# M5_Display_COMM.net
KiCad netlist of a schematic drawn in Altium Designer
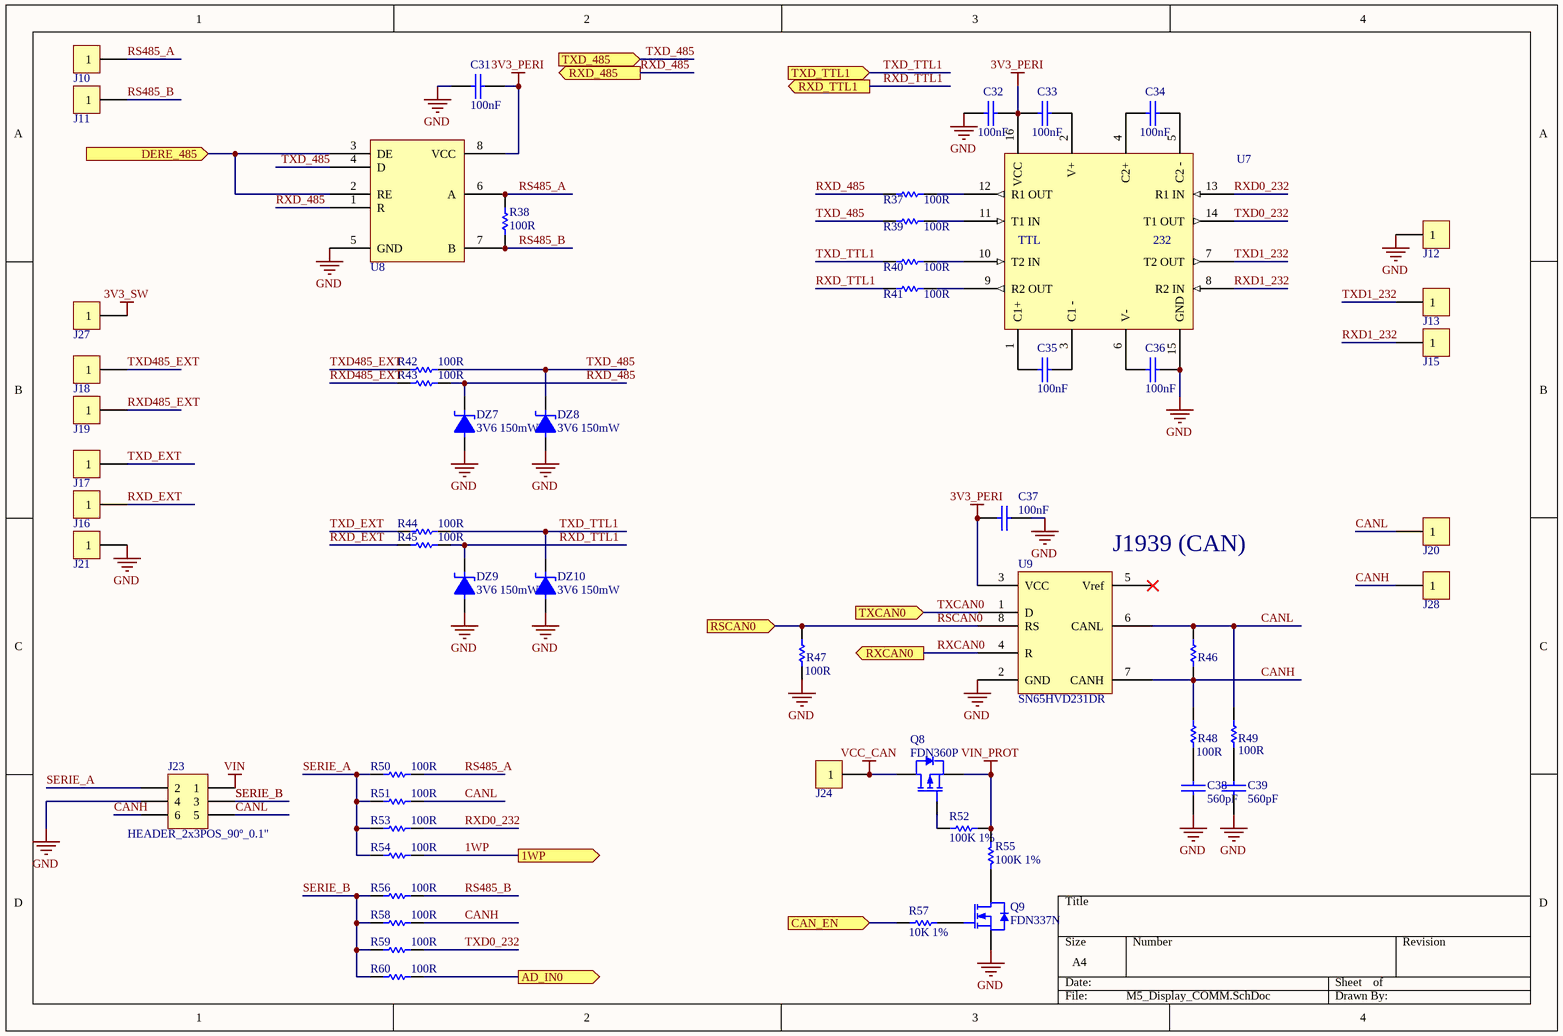
[diagram p0: M5_Display_COMM.SchDoc]

(export (version "E")
  (design (tool "Eeschema 10.0.6"))
  (components
    (comp (ref "C31")
      (value "100nF")
      (footprint "0402")
      (description "CAP0402 100nF 50V X7R")
      (fields
        (field (name "PART NUMBER") "CAP0402_100nF_50V_X7R")
        (field (name "MANUFACTURER") "TDK Corporation")
      )
      (libsource (lib "gl_LIB") (part "CAP"))
    )
    (comp (ref "C32")
      (value "100nF")
      (footprint "0402")
      (description "CAP0402 100nF 50V X7R")
      (fields
        (field (name "PART NUMBER") "CAP0402_100nF_50V_X7R")
        (field (name "MANUFACTURER") "TDK Corporation")
      )
      (libsource (lib "gl_LIB") (part "CAP"))
    )
    (comp (ref "C33")
      (value "100nF")
      (footprint "0402")
      (description "CAP0402 100nF 50V X7R")
      (fields
        (field (name "PART NUMBER") "CAP0402_100nF_50V_X7R")
        (field (name "MANUFACTURER") "TDK Corporation")
      )
      (libsource (lib "gl_LIB") (part "CAP"))
    )
    (comp (ref "C34")
      (value "100nF")
      (footprint "0402")
      (description "CAP0402 100nF 50V X7R")
      (fields
        (field (name "PART NUMBER") "CAP0402_100nF_50V_X7R")
        (field (name "MANUFACTURER") "TDK Corporation")
      )
      (libsource (lib "gl_LIB") (part "CAP"))
    )
    (comp (ref "C35")
      (value "100nF")
      (footprint "0402")
      (description "CAP0402 100nF 50V X7R")
      (fields
        (field (name "PART NUMBER") "CAP0402_100nF_50V_X7R")
        (field (name "MANUFACTURER") "TDK Corporation")
      )
      (libsource (lib "gl_LIB") (part "CAP"))
    )
    (comp (ref "C36")
      (value "100nF")
      (footprint "0402")
      (description "CAP0402 100nF 50V X7R")
      (fields
        (field (name "PART NUMBER") "CAP0402_100nF_50V_X7R")
        (field (name "MANUFACTURER") "TDK Corporation")
      )
      (libsource (lib "gl_LIB") (part "CAP"))
    )
    (comp (ref "C37")
      (value "100nF")
      (footprint "0402")
      (description "CAP0402 100nF 50V X7R")
      (fields (field (name "PART NUMBER") "CAP0402_100nF_50V_X7R"))
      (libsource (lib "gl_LIB") (part "CAP"))
    )
    (comp (ref "C38")
      (value "560pF")
      (footprint "0402")
      (description "CAP0402 560pF 50V NP0")
      (fields (field (name "PART NUMBER") "CAP0402_560pF_NP0"))
      (libsource (lib "gl_LIB") (part "CAP"))
    )
    (comp (ref "C39")
      (value "560pF")
      (footprint "0402")
      (description "CAP0402 560pF 50V NP0")
      (fields (field (name "PART NUMBER") "CAP0402_560pF_NP0"))
      (libsource (lib "gl_LIB") (part "CAP"))
    )
    (comp (ref "DZ7")
      (value "3V6 150mW")
      (footprint "SOD523")
      (description "DIODE ZENER 3.6V 150MW SSMINI2 SOD523")
      (fields
        (field (name "PART NUMBER") "DIO_ZEN_3V6_SOD523")
        (field (name "MANUFACTURER") "Panasonic Electronic Components")
      )
      (libsource (lib "gl_LIB") (part "DIODO ZENER"))
    )
    (comp (ref "DZ8")
      (value "3V6 150mW")
      (footprint "SOD523")
      (description "DIODE ZENER 3.6V 150MW SSMINI2 SOD523")
      (fields
        (field (name "PART NUMBER") "DIO_ZEN_3V6_SOD523")
        (field (name "MANUFACTURER") "Panasonic Electronic Components")
      )
      (libsource (lib "gl_LIB") (part "DIODO ZENER"))
    )
    (comp (ref "DZ9")
      (value "3V6 150mW")
      (footprint "SOD523")
      (description "DIODE ZENER 3.6V 150MW SSMINI2 SOD523")
      (fields
        (field (name "PART NUMBER") "DIO_ZEN_3V6_SOD523")
        (field (name "MANUFACTURER") "Panasonic Electronic Components")
      )
      (libsource (lib "gl_LIB") (part "DIODO ZENER"))
    )
    (comp (ref "DZ10")
      (value "3V6 150mW")
      (footprint "SOD523")
      (description "DIODE ZENER 3.6V 150MW SSMINI2 SOD523")
      (fields
        (field (name "PART NUMBER") "DIO_ZEN_3V6_SOD523")
        (field (name "MANUFACTURER") "Panasonic Electronic Components")
      )
      (libsource (lib "gl_LIB") (part "DIODO ZENER"))
    )
    (comp (ref "J10")
      (value "PIN CABLE")
      (footprint "PIN_CABLE")
      (description "PIN PARA SOLDAR CABLE 1MM")
      (fields (field (name "PART NUMBER") "PIN_1_CABLE_1mm"))
      (libsource (lib "") (part "CON1_TRAMPA_1"))
    )
    (comp (ref "J11")
      (value "PIN CABLE")
      (footprint "PIN_CABLE")
      (description "PIN PARA SOLDAR CABLE 1MM")
      (fields (field (name "PART NUMBER") "PIN_1_CABLE_1mm"))
      (libsource (lib "") (part "CON1_TRAMPA_1"))
    )
    (comp (ref "J12")
      (value "PIN CABLE")
      (footprint "PIN_CABLE")
      (description "PIN PARA SOLDAR CABLE 1MM")
      (fields (field (name "PART NUMBER") "PIN_1_CABLE_1mm"))
      (libsource (lib "gl_LIB") (part "CON1_TRAMPA"))
    )
    (comp (ref "J13")
      (value "PIN CABLE")
      (footprint "PIN_CABLE")
      (description "PIN PARA SOLDAR CABLE 1MM")
      (fields (field (name "PART NUMBER") "PIN_1_CABLE_1mm"))
      (libsource (lib "gl_LIB") (part "CON1_TRAMPA"))
    )
    (comp (ref "J15")
      (value "PIN CABLE")
      (footprint "PIN_CABLE")
      (description "PIN PARA SOLDAR CABLE 1MM")
      (fields (field (name "PART NUMBER") "PIN_1_CABLE_1mm"))
      (libsource (lib "gl_LIB") (part "CON1_TRAMPA"))
    )
    (comp (ref "J16")
      (value "PIN CABLE")
      (footprint "PIN_CABLE")
      (description "PIN PARA SOLDAR CABLE 1MM")
      (fields (field (name "PART NUMBER") "PIN_1_CABLE_1mm"))
      (libsource (lib "") (part "CON1_TRAMPA_1"))
    )
    (comp (ref "J17")
      (value "PIN CABLE")
      (footprint "PIN_CABLE")
      (description "PIN PARA SOLDAR CABLE 1MM")
      (fields (field (name "PART NUMBER") "PIN_1_CABLE_1mm"))
      (libsource (lib "") (part "CON1_TRAMPA_1"))
    )
    (comp (ref "J18")
      (value "PIN CABLE")
      (footprint "PIN_CABLE")
      (description "PIN PARA SOLDAR CABLE 1MM")
      (fields (field (name "PART NUMBER") "PIN_1_CABLE_1mm"))
      (libsource (lib "") (part "CON1_TRAMPA_1"))
    )
    (comp (ref "J19")
      (value "PIN CABLE")
      (footprint "PIN_CABLE")
      (description "PIN PARA SOLDAR CABLE 1MM")
      (fields (field (name "PART NUMBER") "PIN_1_CABLE_1mm"))
      (libsource (lib "") (part "CON1_TRAMPA_1"))
    )
    (comp (ref "J20")
      (value "PIN CABLE")
      (footprint "PIN_CABLE")
      (description "PIN PARA SOLDAR CABLE 1MM")
      (fields (field (name "PART NUMBER") "PIN_1_CABLE_1mm"))
      (libsource (lib "gl_LIB") (part "CON1_TRAMPA"))
    )
    (comp (ref "J21")
      (value "PIN CABLE")
      (footprint "PIN_CABLE")
      (description "PIN PARA SOLDAR CABLE 1MM")
      (fields (field (name "PART NUMBER") "PIN_1_CABLE_1mm"))
      (libsource (lib "") (part "CON1_TRAMPA_1"))
    )
    (comp (ref "J23")
      (value "HEADER_2x3POS_90º_0.1\"")
      (footprint "SIP3_2_90")
      (description "TIRA PINES MACHO 2X3 0,1'' 90º")
      (libsource (lib "gl_LIB") (part "CON3*2"))
    )
    (comp (ref "J24")
      (value "PIN CABLE")
      (footprint "PIN_CABLE")
      (description "PIN PARA SOLDAR CABLE 1MM")
      (fields (field (name "PART NUMBER") "PIN_1_CABLE_1mm"))
      (libsource (lib "") (part "CON1_TRAMPA_1"))
    )
    (comp (ref "J27")
      (value "PIN CABLE")
      (footprint "PIN_CABLE")
      (description "PIN PARA SOLDAR CABLE 1MM")
      (fields (field (name "PART NUMBER") "PIN_1_CABLE_1mm"))
      (libsource (lib "") (part "CON1_TRAMPA_1"))
    )
    (comp (ref "J28")
      (value "PIN CABLE")
      (footprint "PIN_CABLE")
      (description "PIN PARA SOLDAR CABLE 1MM")
      (fields (field (name "PART NUMBER") "PIN_1_CABLE_1mm"))
      (libsource (lib "gl_LIB") (part "CON1_TRAMPA"))
    )
    (comp (ref "Q8")
      (value "FDN360P")
      (footprint "SOT23")
      (description "MOSFET P 30V 2A SSOT3")
      (fields (field (name "PART NUMBER") "FDN360P_SOT23"))
      (libsource (lib "gl_LIB") (part "MOSFET P"))
    )
    (comp (ref "Q9")
      (value "FDN337N")
      (footprint "SOT23")
      (description "MOSFET N-CH 30V 2.2A SSOT3")
      (fields (field (name "PART NUMBER") "FDN337N_SOT23"))
      (libsource (lib "gl_LIB") (part "MOSFET N"))
    )
    (comp (ref "R37")
      (value "100R")
      (footprint "0402")
      (description "RES0402 100R 5%")
      (fields
        (field (name "PART NUMBER") "RES0402_100R_5%")
        (field (name "MANUFACTURER") "Stackpole Electronics Inc")
      )
      (libsource (lib "gl_LIB") (part "RES"))
    )
    (comp (ref "R38")
      (value "100R")
      (footprint "0402")
      (description "RES0402 100R 5%")
      (fields
        (field (name "PART NUMBER") "RES0402_100R_5%")
        (field (name "MANUFACTURER") "Stackpole Electronics Inc")
      )
      (libsource (lib "gl_LIB") (part "RES"))
    )
    (comp (ref "R39")
      (value "100R")
      (footprint "0402")
      (description "RES0402 100R 5%")
      (fields
        (field (name "PART NUMBER") "RES0402_100R_5%")
        (field (name "MANUFACTURER") "Stackpole Electronics Inc")
      )
      (libsource (lib "gl_LIB") (part "RES"))
    )
    (comp (ref "R40")
      (value "100R")
      (footprint "0402")
      (description "RES0402 100R 5%")
      (fields
        (field (name "PART NUMBER") "RES0402_100R_5%")
        (field (name "MANUFACTURER") "Stackpole Electronics Inc")
      )
      (libsource (lib "gl_LIB") (part "RES"))
    )
    (comp (ref "R41")
      (value "100R")
      (footprint "0402")
      (description "RES0402 100R 5%")
      (fields
        (field (name "PART NUMBER") "RES0402_100R_5%")
        (field (name "MANUFACTURER") "Stackpole Electronics Inc")
      )
      (libsource (lib "gl_LIB") (part "RES"))
    )
    (comp (ref "R42")
      (value "100R")
      (footprint "0402")
      (description "RES0402 100R 5%")
      (fields
        (field (name "PART NUMBER") "RES0402_100R_5%")
        (field (name "MANUFACTURER") "Stackpole Electronics Inc")
      )
      (libsource (lib "gl_LIB") (part "RES"))
    )
    (comp (ref "R43")
      (value "100R")
      (footprint "0402")
      (description "RES0402 100R 5%")
      (fields
        (field (name "PART NUMBER") "RES0402_100R_5%")
        (field (name "MANUFACTURER") "Stackpole Electronics Inc")
      )
      (libsource (lib "gl_LIB") (part "RES"))
    )
    (comp (ref "R44")
      (value "100R")
      (footprint "0402")
      (description "RES0402 100R 5%")
      (fields
        (field (name "PART NUMBER") "RES0402_100R_5%")
        (field (name "MANUFACTURER") "Stackpole Electronics Inc")
      )
      (libsource (lib "gl_LIB") (part "RES"))
    )
    (comp (ref "R45")
      (value "100R")
      (footprint "0402")
      (description "RES0402 100R 5%")
      (fields
        (field (name "PART NUMBER") "RES0402_100R_5%")
        (field (name "MANUFACTURER") "Stackpole Electronics Inc")
      )
      (libsource (lib "gl_LIB") (part "RES"))
    )
    (comp (ref "R46")
      (value "120R")
      (footprint "0402")
      (description "RES0402 120R 5%")
      (fields
        (field (name "PART NUMBER") "RES0402_120R_5%")
        (field (name "MANUFACTURER") "Stackpole Electronics Inc")
      )
      (libsource (lib "gl_LIB") (part "RES"))
    )
    (comp (ref "R47")
      (value "100R")
      (footprint "0402")
      (description "RES0402 100R 5%")
      (fields
        (field (name "PART NUMBER") "RES0402_100R_5%")
        (field (name "MANUFACTURER") "Stackpole Electronics Inc")
      )
      (libsource (lib "gl_LIB") (part "RES"))
    )
    (comp (ref "R48")
      (value "100R")
      (footprint "0402")
      (description "RES0402 100R 5%")
      (fields
        (field (name "PART NUMBER") "RES0402_100R_5%")
        (field (name "MANUFACTURER") "Stackpole Electronics Inc")
      )
      (libsource (lib "gl_LIB") (part "RES"))
    )
    (comp (ref "R49")
      (value "100R")
      (footprint "0402")
      (description "RES0402 100R 5%")
      (fields
        (field (name "PART NUMBER") "RES0402_100R_5%")
        (field (name "MANUFACTURER") "Stackpole Electronics Inc")
      )
      (libsource (lib "gl_LIB") (part "RES"))
    )
    (comp (ref "R50")
      (value "100R")
      (footprint "0402")
      (description "RES0402 100R 5%")
      (fields
        (field (name "PART NUMBER") "RES0402_100R_5%")
        (field (name "MANUFACTURER") "Stackpole Electronics Inc")
      )
      (libsource (lib "gl_LIB") (part "RES"))
    )
    (comp (ref "R51")
      (value "100R")
      (footprint "0402")
      (description "RES0402 100R 5%")
      (fields
        (field (name "PART NUMBER") "RES0402_100R_5%")
        (field (name "MANUFACTURER") "Stackpole Electronics Inc")
      )
      (libsource (lib "gl_LIB") (part "RES"))
    )
    (comp (ref "R52")
      (value "100K 1%")
      (footprint "0402")
      (description "RES0402 100K 1%")
      (fields
        (field (name "PART NUMBER") "RES0402_100K_1%")
        (field (name "MANUFACTURER") "Stackpole Electronics Inc")
      )
      (libsource (lib "gl_LIB") (part "RES"))
    )
    (comp (ref "R53")
      (value "100R")
      (footprint "0402")
      (description "RES0402 100R 5%")
      (fields
        (field (name "PART NUMBER") "RES0402_100R_5%")
        (field (name "MANUFACTURER") "Stackpole Electronics Inc")
      )
      (libsource (lib "gl_LIB") (part "RES"))
    )
    (comp (ref "R54")
      (value "100R")
      (footprint "0402")
      (description "RES0402 100R 5%")
      (fields
        (field (name "PART NUMBER") "RES0402_100R_5%")
        (field (name "MANUFACTURER") "Stackpole Electronics Inc")
      )
      (libsource (lib "gl_LIB") (part "RES"))
    )
    (comp (ref "R55")
      (value "100K 1%")
      (footprint "0402")
      (description "RES0402 100K 1%")
      (fields
        (field (name "PART NUMBER") "RES0402_100K_1%")
        (field (name "MANUFACTURER") "Stackpole Electronics Inc")
      )
      (libsource (lib "gl_LIB") (part "RES"))
    )
    (comp (ref "R56")
      (value "100R")
      (footprint "0402")
      (description "RES0402 100R 5%")
      (fields
        (field (name "PART NUMBER") "RES0402_100R_5%")
        (field (name "MANUFACTURER") "Stackpole Electronics Inc")
      )
      (libsource (lib "gl_LIB") (part "RES"))
    )
    (comp (ref "R57")
      (value "10K 1%")
      (footprint "0402")
      (description "RES0402 10K 1%")
      (fields (field (name "PART NUMBER") "RES0402_10K_1%"))
      (libsource (lib "gl_LIB") (part "RES"))
    )
    (comp (ref "R58")
      (value "100R")
      (footprint "0402")
      (description "RES0402 100R 5%")
      (fields
        (field (name "PART NUMBER") "RES0402_100R_5%")
        (field (name "MANUFACTURER") "Stackpole Electronics Inc")
      )
      (libsource (lib "gl_LIB") (part "RES"))
    )
    (comp (ref "R59")
      (value "100R")
      (footprint "0402")
      (description "RES0402 100R 5%")
      (fields
        (field (name "PART NUMBER") "RES0402_100R_5%")
        (field (name "MANUFACTURER") "Stackpole Electronics Inc")
      )
      (libsource (lib "gl_LIB") (part "RES"))
    )
    (comp (ref "R60")
      (value "100R")
      (footprint "0402")
      (description "RES0402 100R 5%")
      (fields
        (field (name "PART NUMBER") "RES0402_100R_5%")
        (field (name "MANUFACTURER") "Stackpole Electronics Inc")
      )
      (libsource (lib "gl_LIB") (part "RES"))
    )
    (comp (ref "U7")
      (value "ST3232ECDR")
      (footprint "SOIC16N")
      (description "IC DRVR/RCVR RS232 ESD 16-SOIC")
      (fields
        (field (name "PART NUMBER") "ST3232_SOIC16N")
        (field (name "MANUFACTURER") "STMicroelectronics")
      )
      (libsource (lib "gl_LIB") (part "MAX3232"))
    )
    (comp (ref "U8")
      (value "ST3485EBDR")
      (footprint "SO8")
      (description "IC TXRX 3.3V RS485/422 8 SOIC")
      (fields (field (name "PART NUMBER") "ST3485_SO8") (field (name "MANUFACTURER") "STMicroelectronics"))
      (libsource (lib "gl_LIB") (part "ST3485"))
    )
    (comp (ref "U9")
      (value "SN65HVD231DR")
      (footprint "SO8")
      (description "IC CAN TRANSCEIVER W/ SLEEP MODE 3.3V 8-SOIC")
      (fields (field (name "PART NUMBER") "SN65HVD231_SO8"))
      (libsource (lib "gl_LIB") (part "SN65HVD231"))
    )
  )
  (nets
    (net (code "1") (name "/1WP") (class "Default")
      (node (ref "R54") (pin "2") (pinfunction "2_2") (pintype "passive"))
    )
    (net (code "2") (name "/AD_IN0") (class "Default")
      (node (ref "R60") (pin "2") (pinfunction "2_2") (pintype "passive"))
    )
    (net (code "3") (name "/CANH") (class "Default")
      (node (ref "J23") (pin "6") (pinfunction "6_6") (pintype "passive"))
      (node (ref "J28") (pin "1") (pinfunction "1_1") (pintype "passive"))
      (node (ref "R46") (pin "1") (pinfunction "1_1") (pintype "passive"))
      (node (ref "R48") (pin "2") (pinfunction "2_2") (pintype "passive"))
      (node (ref "R58") (pin "2") (pinfunction "2_2") (pintype "passive"))
      (node (ref "U9") (pin "7") (pinfunction "CANH_7") (pintype "passive"))
    )
    (net (code "4") (name "/CANL") (class "Default")
      (node (ref "J20") (pin "1") (pinfunction "1_1") (pintype "passive"))
      (node (ref "J23") (pin "5") (pinfunction "5_5") (pintype "passive"))
      (node (ref "R46") (pin "2") (pinfunction "2_2") (pintype "passive"))
      (node (ref "R49") (pin "2") (pinfunction "2_2") (pintype "passive"))
      (node (ref "R51") (pin "2") (pinfunction "2_2") (pintype "passive"))
      (node (ref "U9") (pin "6") (pinfunction "CANL_6") (pintype "passive"))
    )
    (net (code "5") (name "/CAN_EN") (class "Default")
      (node (ref "R57") (pin "2") (pinfunction "2_2") (pintype "passive"))
    )
    (net (code "6") (name "/DERE_485") (class "Default")
      (node (ref "U8") (pin "2") (pinfunction "RE_2") (pintype "passive"))
      (node (ref "U8") (pin "3") (pinfunction "DE_3") (pintype "passive"))
    )
    (net (code "7") (name "/RS485_A") (class "Default")
      (node (ref "J10") (pin "1") (pinfunction "1_1") (pintype "passive"))
      (node (ref "R38") (pin "2") (pinfunction "2_2") (pintype "passive"))
      (node (ref "R50") (pin "2") (pinfunction "2_2") (pintype "passive"))
      (node (ref "U8") (pin "6") (pinfunction "A_6") (pintype "passive"))
    )
    (net (code "8") (name "/RS485_B") (class "Default")
      (node (ref "J11") (pin "1") (pinfunction "1_1") (pintype "passive"))
      (node (ref "R38") (pin "1") (pinfunction "1_1") (pintype "passive"))
      (node (ref "R56") (pin "2") (pinfunction "2_2") (pintype "passive"))
      (node (ref "U8") (pin "7") (pinfunction "B_7") (pintype "passive"))
    )
    (net (code "9") (name "/RSCAN0") (class "Default")
      (node (ref "R47") (pin "2") (pinfunction "2_2") (pintype "passive"))
      (node (ref "U9") (pin "8") (pinfunction "RS_8") (pintype "passive"))
    )
    (net (code "10") (name "/RXCAN0") (class "Default")
      (node (ref "U9") (pin "4") (pinfunction "R_4") (pintype "passive"))
    )
    (net (code "11") (name "/RXD0_232") (class "Default")
      (node (ref "R53") (pin "2") (pinfunction "2_2") (pintype "passive"))
      (node (ref "U7") (pin "13") (pinfunction "R1_IN_13") (pintype "input"))
    )
    (net (code "12") (name "/RXD1_232") (class "Default")
      (node (ref "J15") (pin "1") (pinfunction "1_1") (pintype "passive"))
      (node (ref "U7") (pin "8") (pinfunction "R2_IN_8") (pintype "input"))
    )
    (net (code "13") (name "/RXD485_EXT") (class "Default")
      (node (ref "J19") (pin "1") (pinfunction "1_1") (pintype "passive"))
      (node (ref "R43") (pin "1") (pinfunction "1_1") (pintype "passive"))
    )
    (net (code "14") (name "/RXD_485") (class "Default")
      (node (ref "DZ7") (pin "2") (pinfunction "2_2") (pintype "passive"))
      (node (ref "R37") (pin "1") (pinfunction "1_1") (pintype "passive"))
      (node (ref "R43") (pin "2") (pinfunction "2_2") (pintype "passive"))
      (node (ref "U8") (pin "1") (pinfunction "R_1") (pintype "passive"))
    )
    (net (code "15") (name "/RXD_EXT") (class "Default")
      (node (ref "J16") (pin "1") (pinfunction "1_1") (pintype "passive"))
      (node (ref "R45") (pin "1") (pinfunction "1_1") (pintype "passive"))
    )
    (net (code "16") (name "/RXD_TTL1") (class "Default")
      (node (ref "DZ9") (pin "2") (pinfunction "2_2") (pintype "passive"))
      (node (ref "R41") (pin "1") (pinfunction "1_1") (pintype "passive"))
      (node (ref "R45") (pin "2") (pinfunction "2_2") (pintype "passive"))
    )
    (net (code "17") (name "/SERIE_A") (class "Default")
      (node (ref "J23") (pin "2") (pinfunction "2_2") (pintype "passive"))
      (node (ref "R50") (pin "1") (pinfunction "1_1") (pintype "passive"))
      (node (ref "R51") (pin "1") (pinfunction "1_1") (pintype "passive"))
      (node (ref "R53") (pin "1") (pinfunction "1_1") (pintype "passive"))
      (node (ref "R54") (pin "1") (pinfunction "1_1") (pintype "passive"))
    )
    (net (code "18") (name "/SERIE_B") (class "Default")
      (node (ref "J23") (pin "3") (pinfunction "3_3") (pintype "passive"))
      (node (ref "R56") (pin "1") (pinfunction "1_1") (pintype "passive"))
      (node (ref "R58") (pin "1") (pinfunction "1_1") (pintype "passive"))
      (node (ref "R59") (pin "1") (pinfunction "1_1") (pintype "passive"))
      (node (ref "R60") (pin "1") (pinfunction "1_1") (pintype "passive"))
    )
    (net (code "19") (name "/TXCAN0") (class "Default")
      (node (ref "U9") (pin "1") (pinfunction "D_1") (pintype "passive"))
    )
    (net (code "20") (name "/TXD0_232") (class "Default")
      (node (ref "R59") (pin "2") (pinfunction "2_2") (pintype "passive"))
      (node (ref "U7") (pin "14") (pinfunction "T1_OUT_14") (pintype "output"))
    )
    (net (code "21") (name "/TXD1_232") (class "Default")
      (node (ref "J13") (pin "1") (pinfunction "1_1") (pintype "passive"))
      (node (ref "U7") (pin "7") (pinfunction "T2_OUT_7") (pintype "output"))
    )
    (net (code "22") (name "/TXD485_EXT") (class "Default")
      (node (ref "J18") (pin "1") (pinfunction "1_1") (pintype "passive"))
      (node (ref "R42") (pin "1") (pinfunction "1_1") (pintype "passive"))
    )
    (net (code "23") (name "/TXD_485") (class "Default")
      (node (ref "DZ8") (pin "2") (pinfunction "2_2") (pintype "passive"))
      (node (ref "R39") (pin "2") (pinfunction "2_2") (pintype "passive"))
      (node (ref "R42") (pin "2") (pinfunction "2_2") (pintype "passive"))
      (node (ref "U8") (pin "4") (pinfunction "D_4") (pintype "passive"))
    )
    (net (code "24") (name "/TXD_EXT") (class "Default")
      (node (ref "J17") (pin "1") (pinfunction "1_1") (pintype "passive"))
      (node (ref "R44") (pin "1") (pinfunction "1_1") (pintype "passive"))
    )
    (net (code "25") (name "/TXD_TTL1") (class "Default")
      (node (ref "DZ10") (pin "2") (pinfunction "2_2") (pintype "passive"))
      (node (ref "R40") (pin "1") (pinfunction "1_1") (pintype "passive"))
      (node (ref "R44") (pin "2") (pinfunction "2_2") (pintype "passive"))
    )
    (net (code "26") (name "3V3_PERI") (class "Default")
      (node (ref "C31") (pin "1") (pinfunction "1_1") (pintype "passive"))
      (node (ref "C32") (pin "2") (pinfunction "2_2") (pintype "passive"))
      (node (ref "C33") (pin "1") (pinfunction "1_1") (pintype "passive"))
      (node (ref "C37") (pin "1") (pinfunction "1_1") (pintype "passive"))
      (node (ref "U7") (pin "16") (pinfunction "VCC_16") (pintype "power_in"))
      (node (ref "U8") (pin "8") (pinfunction "VCC_8") (pintype "passive"))
      (node (ref "U9") (pin "3") (pinfunction "VCC_3") (pintype "passive"))
    )
    (net (code "27") (name "3V3_SW") (class "Default")
      (node (ref "J27") (pin "1") (pinfunction "1_1") (pintype "passive"))
    )
    (net (code "28") (name "GND") (class "Default")
      (node (ref "C31") (pin "2") (pinfunction "2_2") (pintype "passive"))
      (node (ref "C32") (pin "1") (pinfunction "1_1") (pintype "passive"))
      (node (ref "C36") (pin "2") (pinfunction "2_2") (pintype "passive"))
      (node (ref "C37") (pin "2") (pinfunction "2_2") (pintype "passive"))
      (node (ref "C38") (pin "1") (pinfunction "1_1") (pintype "passive"))
      (node (ref "C39") (pin "1") (pinfunction "1_1") (pintype "passive"))
      (node (ref "DZ10") (pin "1") (pinfunction "1_1") (pintype "passive"))
      (node (ref "DZ7") (pin "1") (pinfunction "1_1") (pintype "passive"))
      (node (ref "DZ8") (pin "1") (pinfunction "1_1") (pintype "passive"))
      (node (ref "DZ9") (pin "1") (pinfunction "1_1") (pintype "passive"))
      (node (ref "J12") (pin "1") (pinfunction "1_1") (pintype "passive"))
      (node (ref "J21") (pin "1") (pinfunction "1_1") (pintype "passive"))
      (node (ref "J23") (pin "4") (pinfunction "4_4") (pintype "passive"))
      (node (ref "Q9") (pin "3") (pinfunction "S_3") (pintype "passive"))
      (node (ref "R47") (pin "1") (pinfunction "1_1") (pintype "passive"))
      (node (ref "U7") (pin "15") (pinfunction "GND_15") (pintype "power_in"))
      (node (ref "U8") (pin "5") (pinfunction "GND_5") (pintype "passive"))
      (node (ref "U9") (pin "2") (pinfunction "GND_2") (pintype "passive"))
    )
    (net (code "29") (name "Net-(C38-Pad2)") (class "Default")
      (node (ref "C38") (pin "2") (pinfunction "2_2") (pintype "passive"))
      (node (ref "R48") (pin "1") (pinfunction "1_1") (pintype "passive"))
    )
    (net (code "30") (name "Net-(C39-Pad2)") (class "Default")
      (node (ref "C39") (pin "2") (pinfunction "2_2") (pintype "passive"))
      (node (ref "R49") (pin "1") (pinfunction "1_1") (pintype "passive"))
    )
    (net (code "31") (name "Net-(Q8-G)") (class "Default")
      (node (ref "Q8") (pin "1") (pinfunction "G_1") (pintype "passive"))
      (node (ref "R52") (pin "1") (pinfunction "1_1") (pintype "passive"))
    )
    (net (code "32") (name "Net-(Q9-D)") (class "Default")
      (node (ref "Q9") (pin "2") (pinfunction "D_2") (pintype "passive"))
      (node (ref "R55") (pin "1") (pinfunction "1_1") (pintype "passive"))
    )
    (net (code "33") (name "Net-(Q9-G)") (class "Default")
      (node (ref "Q9") (pin "1") (pinfunction "G_1") (pintype "passive"))
      (node (ref "R57") (pin "1") (pinfunction "1_1") (pintype "passive"))
    )
    (net (code "34") (name "Net-(U7-C1+)") (class "Default")
      (node (ref "C35") (pin "1") (pinfunction "1_1") (pintype "passive"))
      (node (ref "U7") (pin "1") (pinfunction "C1+_1") (pintype "passive"))
    )
    (net (code "35") (name "Net-(U7-C1_-)") (class "Default")
      (node (ref "C35") (pin "2") (pinfunction "2_2") (pintype "passive"))
      (node (ref "U7") (pin "3") (pinfunction "C1_-_3") (pintype "passive"))
    )
    (net (code "36") (name "Net-(U7-C2+)") (class "Default")
      (node (ref "C34") (pin "1") (pinfunction "1_1") (pintype "passive"))
      (node (ref "U7") (pin "4") (pinfunction "C2+_4") (pintype "passive"))
    )
    (net (code "37") (name "Net-(U7-C2_-)") (class "Default")
      (node (ref "C34") (pin "2") (pinfunction "2_2") (pintype "passive"))
      (node (ref "U7") (pin "5") (pinfunction "C2_-_5") (pintype "passive"))
    )
    (net (code "38") (name "Net-(U7-R1_OUT)") (class "Default")
      (node (ref "R37") (pin "2") (pinfunction "2_2") (pintype "passive"))
      (node (ref "U7") (pin "12") (pinfunction "R1_OUT_12") (pintype "output"))
    )
    (net (code "39") (name "Net-(U7-R2_OUT)") (class "Default")
      (node (ref "R41") (pin "2") (pinfunction "2_2") (pintype "passive"))
      (node (ref "U7") (pin "9") (pinfunction "R2_OUT_9") (pintype "output"))
    )
    (net (code "40") (name "Net-(U7-T1_IN)") (class "Default")
      (node (ref "R39") (pin "1") (pinfunction "1_1") (pintype "passive"))
      (node (ref "U7") (pin "11") (pinfunction "T1_IN_11") (pintype "input"))
    )
    (net (code "41") (name "Net-(U7-T2_IN)") (class "Default")
      (node (ref "R40") (pin "2") (pinfunction "2_2") (pintype "passive"))
      (node (ref "U7") (pin "10") (pinfunction "T2_IN_10") (pintype "input"))
    )
    (net (code "42") (name "Net-(U7-V+)") (class "Default")
      (node (ref "C33") (pin "2") (pinfunction "2_2") (pintype "passive"))
      (node (ref "U7") (pin "2") (pinfunction "V+_2") (pintype "power_in"))
    )
    (net (code "43") (name "Net-(U7-V-)") (class "Default")
      (node (ref "C36") (pin "1") (pinfunction "1_1") (pintype "passive"))
      (node (ref "U7") (pin "6") (pinfunction "V-_6") (pintype "power_in"))
    )
    (net (code "44") (name "VCC_CAN") (class "Default")
      (node (ref "J24") (pin "1") (pinfunction "1_1") (pintype "passive"))
      (node (ref "Q8") (pin "2") (pinfunction "D_2") (pintype "passive"))
    )
    (net (code "45") (name "VIN") (class "Default")
      (node (ref "J23") (pin "1") (pinfunction "1_1") (pintype "passive"))
    )
    (net (code "46") (name "VIN_PROT") (class "Default")
      (node (ref "Q8") (pin "3") (pinfunction "S_3") (pintype "passive"))
      (node (ref "R52") (pin "2") (pinfunction "2_2") (pintype "passive"))
      (node (ref "R55") (pin "2") (pinfunction "2_2") (pintype "passive"))
    )
    (net (code "47") (name "unconnected-(U9-Vref-Pad5)") (class "Default")
      (node (ref "U9") (pin "5") (pinfunction "Vref_5") (pintype "passive+no_connect"))
    )
  )
)
